# ver9.net
KiCad netlist of a schematic drawn in EAGLE
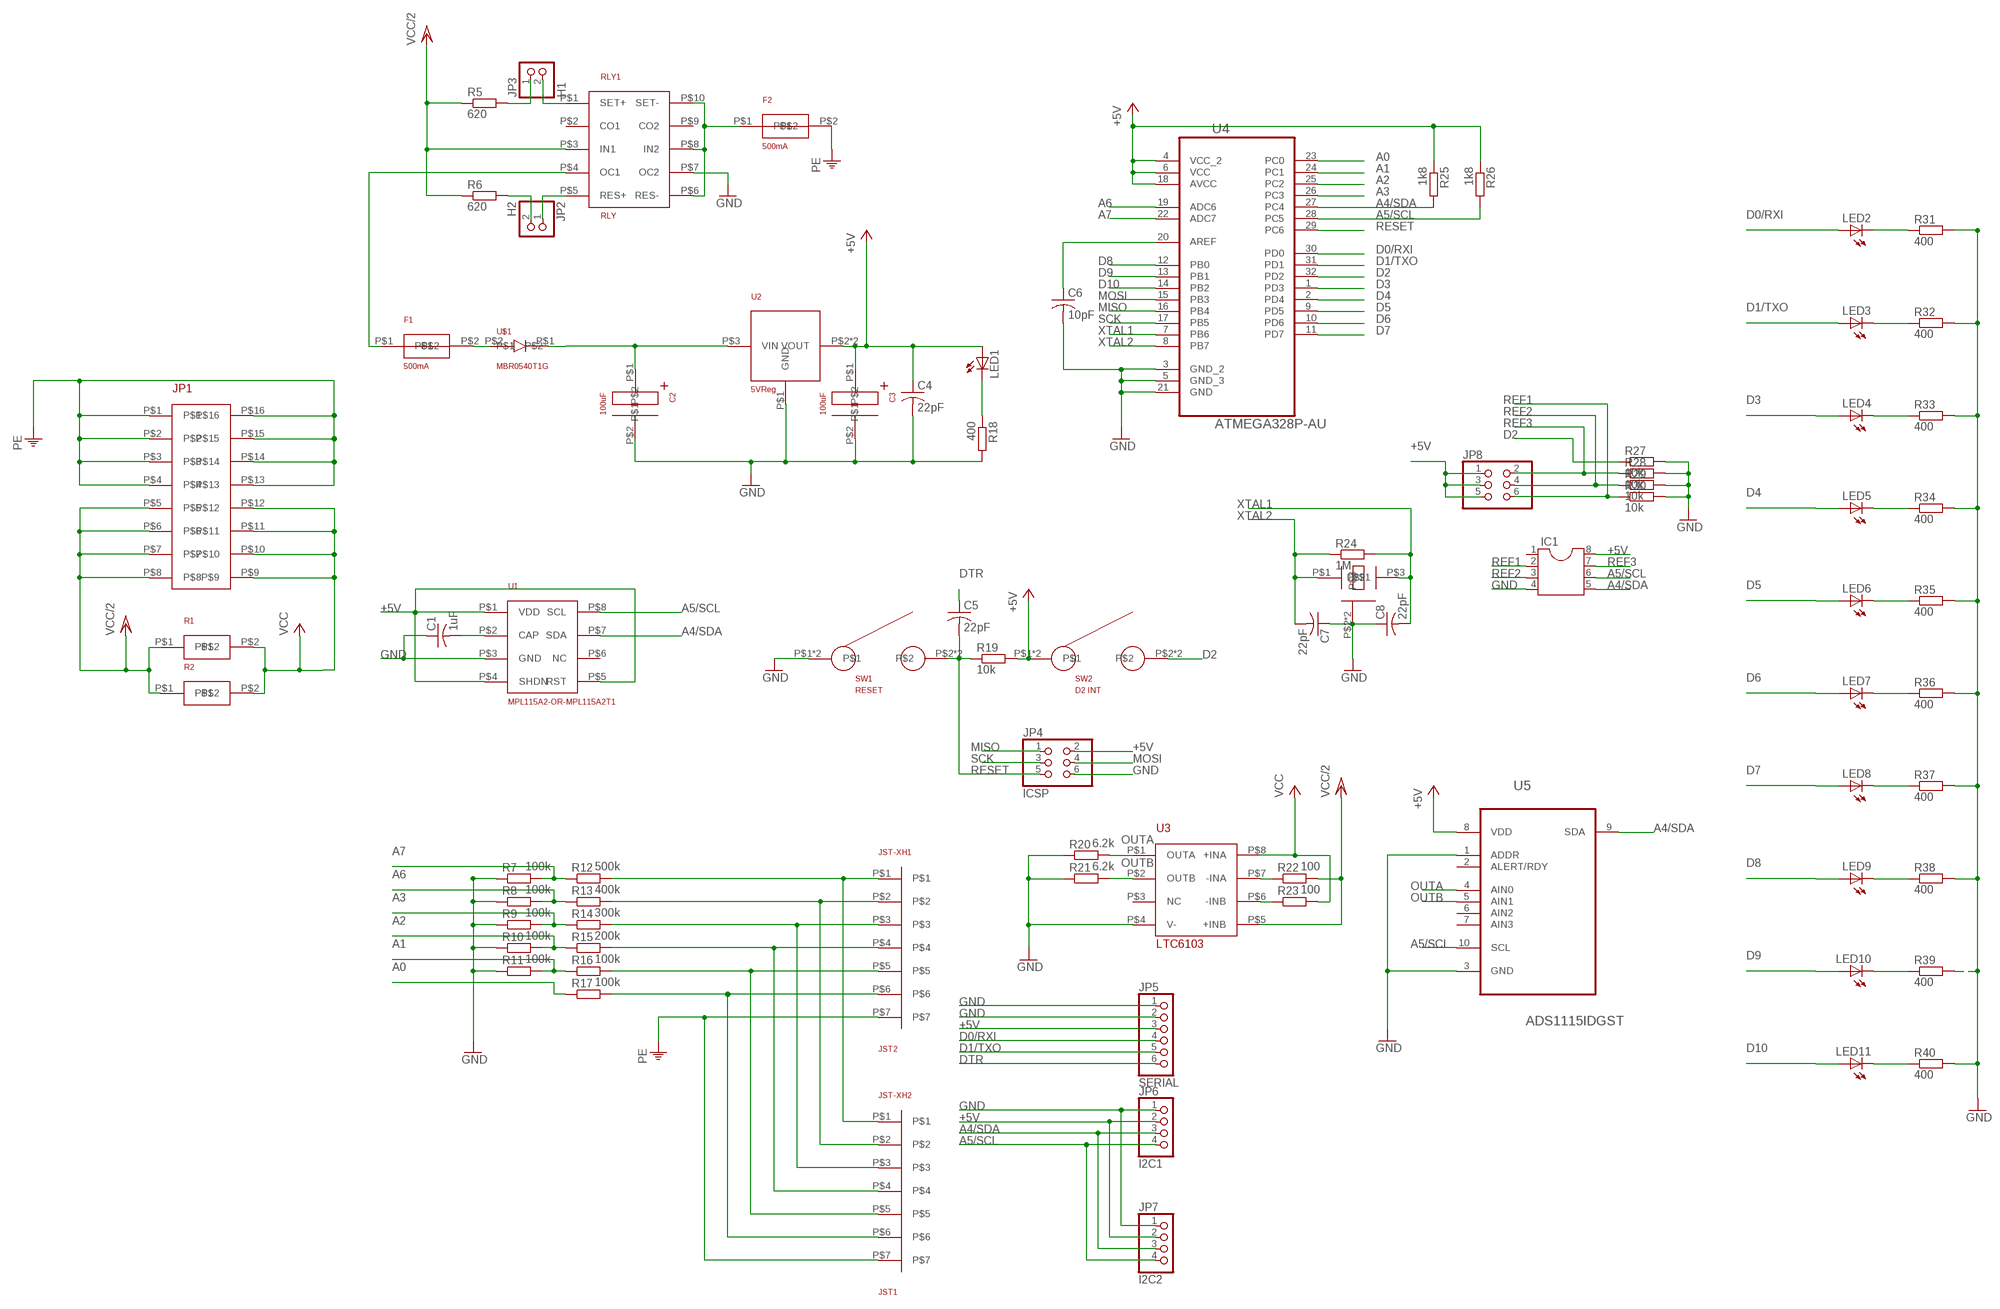
[diagram p0: schematic, sheet 1]

(export (version "E")
  (design (tool "Eeschema 10.0.6"))
  (components
    (comp (ref "C1")
      (value "1uF")
      (footprint "eagle-import:C1206")
      (libsource (lib "eagle-import") (part "C-USC1206"))
    )
    (comp (ref "C2")
      (value "100uF")
      (footprint "eagle-import:EEEFTH101XAP")
      (libsource (lib "eagle-import") (part "EEEFTH101XAP"))
    )
    (comp (ref "C3")
      (value "100uF")
      (footprint "eagle-import:EEEFTH101XAP")
      (libsource (lib "eagle-import") (part "EEEFTH101XAP"))
    )
    (comp (ref "C4")
      (value "22pF")
      (footprint "eagle-import:C1206")
      (libsource (lib "eagle-import") (part "C-USC1206"))
    )
    (comp (ref "C5")
      (value "22pF")
      (footprint "eagle-import:C1206")
      (libsource (lib "eagle-import") (part "C-USC1206"))
    )
    (comp (ref "C6")
      (value "10pF")
      (footprint "eagle-import:C1206")
      (libsource (lib "eagle-import") (part "C-USC1206"))
    )
    (comp (ref "C7")
      (value "22pF")
      (footprint "eagle-import:C1206")
      (libsource (lib "eagle-import") (part "C-USC1206"))
    )
    (comp (ref "C8")
      (value "22pF")
      (footprint "eagle-import:C1206")
      (libsource (lib "eagle-import") (part "C-USC1206"))
    )
    (comp (ref "F1")
      (value "500mA")
      (footprint "eagle-import:MF-MSMF050-2")
      (libsource (lib "eagle-import") (part "MF-MSMF050-2"))
    )
    (comp (ref "F2")
      (value "500mA")
      (footprint "eagle-import:0154.500DR-FUSE-0453.500")
      (libsource (lib "eagle-import") (part "0154.500DR-FUSE-0453.500"))
    )
    (comp (ref "IC1")
      (value "DIL8S")
      (footprint "eagle-import:SOCKET-08")
      (libsource (lib "eagle-import") (part "DIL8S"))
    )
    (comp (ref "JP1")
      (value "39-29-1167-MOLEX")
      (footprint "eagle-import:39-29-1167-MOLEX")
      (libsource (lib "eagle-import") (part "39-29-1167-MOLEX"))
    )
    (comp (ref "JP2")
      (value "H2")
      (footprint "eagle-import:1X02")
      (libsource (lib "eagle-import") (part "PINHD-1X2"))
    )
    (comp (ref "JP3")
      (value "H1")
      (footprint "eagle-import:1X02")
      (libsource (lib "eagle-import") (part "PINHD-1X2"))
    )
    (comp (ref "JP4")
      (value "ICSP")
      (footprint "eagle-import:2X03")
      (libsource (lib "eagle-import") (part "PINHD-2X3"))
    )
    (comp (ref "JP5")
      (value "SERIAL")
      (footprint "eagle-import:1X06")
      (libsource (lib "eagle-import") (part "PINHD-1X6"))
    )
    (comp (ref "JP6")
      (value "I2C1")
      (footprint "eagle-import:1X04")
      (libsource (lib "eagle-import") (part "PINHD-1X4"))
    )
    (comp (ref "JP7")
      (value "I2C2")
      (footprint "eagle-import:1X04")
      (libsource (lib "eagle-import") (part "PINHD-1X4"))
    )
    (comp (ref "JP8")
      (value "PINHD-2X3")
      (footprint "eagle-import:2X03")
      (libsource (lib "eagle-import") (part "PINHD-2X3"))
    )
    (comp (ref "JST-XH1")
      (value "JST2")
      (footprint "eagle-import:JSTXH-7PIN")
      (libsource (lib "eagle-import") (part "JSTXH-7PIN"))
    )
    (comp (ref "JST-XH2")
      (value "JST1")
      (footprint "eagle-import:JSTXH-7PIN")
      (libsource (lib "eagle-import") (part "JSTXH-7PIN"))
    )
    (comp (ref "LED1")
      (value "LED1206")
      (footprint "eagle-import:LED-1206")
      (libsource (lib "eagle-import") (part "LED1206"))
    )
    (comp (ref "LED2")
      (value "LED1206")
      (footprint "eagle-import:LED-1206")
      (libsource (lib "eagle-import") (part "LED1206"))
    )
    (comp (ref "LED3")
      (value "LED1206")
      (footprint "eagle-import:LED-1206")
      (libsource (lib "eagle-import") (part "LED1206"))
    )
    (comp (ref "LED4")
      (value "LED1206")
      (footprint "eagle-import:LED-1206")
      (libsource (lib "eagle-import") (part "LED1206"))
    )
    (comp (ref "LED5")
      (value "LED1206")
      (footprint "eagle-import:LED-1206")
      (libsource (lib "eagle-import") (part "LED1206"))
    )
    (comp (ref "LED6")
      (value "LED1206")
      (footprint "eagle-import:LED-1206")
      (libsource (lib "eagle-import") (part "LED1206"))
    )
    (comp (ref "LED7")
      (value "LED1206")
      (footprint "eagle-import:LED-1206")
      (libsource (lib "eagle-import") (part "LED1206"))
    )
    (comp (ref "LED8")
      (value "LED1206")
      (footprint "eagle-import:LED-1206")
      (libsource (lib "eagle-import") (part "LED1206"))
    )
    (comp (ref "LED9")
      (value "LED1206")
      (footprint "eagle-import:LED-1206")
      (libsource (lib "eagle-import") (part "LED1206"))
    )
    (comp (ref "LED10")
      (value "LED1206")
      (footprint "eagle-import:LED-1206")
      (libsource (lib "eagle-import") (part "LED1206"))
    )
    (comp (ref "LED11")
      (value "LED1206")
      (footprint "eagle-import:LED-1206")
      (libsource (lib "eagle-import") (part "LED1206"))
    )
    (comp (ref "R1")
      (value "OARSXPR002FLF")
      (footprint "eagle-import:OARSXPR002FLF")
      (libsource (lib "eagle-import") (part "OARSXPR002FLF"))
    )
    (comp (ref "R2")
      (value "OARSXPR002FLF")
      (footprint "eagle-import:OARSXPR002FLF")
      (libsource (lib "eagle-import") (part "OARSXPR002FLF"))
    )
    (comp (ref "R5")
      (value "620")
      (footprint "eagle-import:R1206")
      (libsource (lib "eagle-import") (part "R-EU_R1206"))
    )
    (comp (ref "R6")
      (value "620")
      (footprint "eagle-import:R1206")
      (libsource (lib "eagle-import") (part "R-EU_R1206"))
    )
    (comp (ref "R7")
      (value "100k")
      (footprint "eagle-import:R1206")
      (libsource (lib "eagle-import") (part "R-EU_R1206"))
    )
    (comp (ref "R8")
      (value "100k")
      (footprint "eagle-import:R1206")
      (libsource (lib "eagle-import") (part "R-EU_R1206"))
    )
    (comp (ref "R9")
      (value "100k")
      (footprint "eagle-import:R1206")
      (libsource (lib "eagle-import") (part "R-EU_R1206"))
    )
    (comp (ref "R10")
      (value "100k")
      (footprint "eagle-import:R1206")
      (libsource (lib "eagle-import") (part "R-EU_R1206"))
    )
    (comp (ref "R11")
      (value "100k")
      (footprint "eagle-import:R1206")
      (libsource (lib "eagle-import") (part "R-EU_R1206"))
    )
    (comp (ref "R12")
      (value "500k")
      (footprint "eagle-import:R1206")
      (libsource (lib "eagle-import") (part "R-EU_R1206"))
    )
    (comp (ref "R13")
      (value "400k")
      (footprint "eagle-import:R1206")
      (libsource (lib "eagle-import") (part "R-EU_R1206"))
    )
    (comp (ref "R14")
      (value "300k")
      (footprint "eagle-import:R1206")
      (libsource (lib "eagle-import") (part "R-EU_R1206"))
    )
    (comp (ref "R15")
      (value "200k")
      (footprint "eagle-import:R1206")
      (libsource (lib "eagle-import") (part "R-EU_R1206"))
    )
    (comp (ref "R16")
      (value "100k")
      (footprint "eagle-import:R1206")
      (libsource (lib "eagle-import") (part "R-EU_R1206"))
    )
    (comp (ref "R17")
      (value "100k")
      (footprint "eagle-import:R1206")
      (libsource (lib "eagle-import") (part "R-EU_R1206"))
    )
    (comp (ref "R18")
      (value "400")
      (footprint "eagle-import:R1206")
      (libsource (lib "eagle-import") (part "R-EU_R1206"))
    )
    (comp (ref "R19")
      (value "10k")
      (footprint "eagle-import:R1206")
      (libsource (lib "eagle-import") (part "R-EU_R1206"))
    )
    (comp (ref "R20")
      (value "6.2k")
      (footprint "eagle-import:R1206")
      (libsource (lib "eagle-import") (part "R-EU_R1206"))
    )
    (comp (ref "R21")
      (value "6.2k")
      (footprint "eagle-import:R1206")
      (libsource (lib "eagle-import") (part "R-EU_R1206"))
    )
    (comp (ref "R22")
      (value "100")
      (footprint "eagle-import:R1206")
      (libsource (lib "eagle-import") (part "R-EU_R1206"))
    )
    (comp (ref "R23")
      (value "100")
      (footprint "eagle-import:R1206")
      (libsource (lib "eagle-import") (part "R-EU_R1206"))
    )
    (comp (ref "R24")
      (value "1M")
      (footprint "eagle-import:R1206")
      (libsource (lib "eagle-import") (part "R-EU_R1206"))
    )
    (comp (ref "R25")
      (value "1k8")
      (footprint "eagle-import:R1206")
      (libsource (lib "eagle-import") (part "R-EU_R1206"))
    )
    (comp (ref "R26")
      (value "1k8")
      (footprint "eagle-import:R1206")
      (libsource (lib "eagle-import") (part "R-EU_R1206"))
    )
    (comp (ref "R27")
      (value "10k")
      (footprint "eagle-import:R1206")
      (libsource (lib "eagle-import") (part "R-EU_R1206"))
    )
    (comp (ref "R28")
      (value "10k")
      (footprint "eagle-import:R1206")
      (libsource (lib "eagle-import") (part "R-EU_R1206"))
    )
    (comp (ref "R29")
      (value "10k")
      (footprint "eagle-import:R1206")
      (libsource (lib "eagle-import") (part "R-EU_R1206"))
    )
    (comp (ref "R30")
      (value "10k")
      (footprint "eagle-import:R1206")
      (libsource (lib "eagle-import") (part "R-EU_R1206"))
    )
    (comp (ref "R31")
      (value "400")
      (footprint "eagle-import:R1206")
      (libsource (lib "eagle-import") (part "R-EU_R1206"))
    )
    (comp (ref "R32")
      (value "400")
      (footprint "eagle-import:R1206")
      (libsource (lib "eagle-import") (part "R-EU_R1206"))
    )
    (comp (ref "R33")
      (value "400")
      (footprint "eagle-import:R1206")
      (libsource (lib "eagle-import") (part "R-EU_R1206"))
    )
    (comp (ref "R34")
      (value "400")
      (footprint "eagle-import:R1206")
      (libsource (lib "eagle-import") (part "R-EU_R1206"))
    )
    (comp (ref "R35")
      (value "400")
      (footprint "eagle-import:R1206")
      (libsource (lib "eagle-import") (part "R-EU_R1206"))
    )
    (comp (ref "R36")
      (value "400")
      (footprint "eagle-import:R1206")
      (libsource (lib "eagle-import") (part "R-EU_R1206"))
    )
    (comp (ref "R37")
      (value "400")
      (footprint "eagle-import:R1206")
      (libsource (lib "eagle-import") (part "R-EU_R1206"))
    )
    (comp (ref "R38")
      (value "400")
      (footprint "eagle-import:R1206")
      (libsource (lib "eagle-import") (part "R-EU_R1206"))
    )
    (comp (ref "R39")
      (value "400")
      (footprint "eagle-import:R1206")
      (libsource (lib "eagle-import") (part "R-EU_R1206"))
    )
    (comp (ref "R40")
      (value "400")
      (footprint "eagle-import:R1206")
      (libsource (lib "eagle-import") (part "R-EU_R1206"))
    )
    (comp (ref "RLY1")
      (value "RLY")
      (footprint "eagle-import:3-1393788-3")
      (libsource (lib "eagle-import") (part "3-1393788-3"))
    )
    (comp (ref "SW1")
      (value "RESET")
      (footprint "eagle-import:MC32829")
      (libsource (lib "eagle-import") (part "MC32829"))
    )
    (comp (ref "SW2")
      (value "D2 INT")
      (footprint "eagle-import:MC32829")
      (libsource (lib "eagle-import") (part "MC32829"))
    )
    (comp (ref "U$1")
      (value "MBR0540T1G")
      (footprint "eagle-import:MBR0540T1G")
      (libsource (lib "eagle-import") (part "MBR0540T1G"))
    )
    (comp (ref "U1")
      (value "MPL115A2-OR-MPL115A2T1")
      (footprint "eagle-import:MPL115A2-OR-MPL115A2T1")
      (libsource (lib "eagle-import") (part "MPL115A2-OR-MPL115A2T1"))
    )
    (comp (ref "U2")
      (value "5VReg")
      (footprint "eagle-import:NX1117C50Z")
      (libsource (lib "eagle-import") (part "NX1117C50Z"))
    )
    (comp (ref "U3")
      (value "LTC6103")
      (footprint "eagle-import:LTC6103CMS8#PBF")
      (libsource (lib "eagle-import") (part "LTC6103CMS8#PBF"))
    )
    (comp (ref "U4")
      (value "ATMEGA328P-AU")
      (footprint "eagle-import:QFP80P900X900X120-32N")
      (libsource (lib "eagle-import") (part "ATMEGA328P-AU"))
    )
    (comp (ref "U5")
      (value "ADS1115IDGST")
      (footprint "eagle-import:SOP50P490X110-10N")
      (libsource (lib "eagle-import") (part "ADS1115IDGST"))
    )
    (comp (ref "XT1")
      (value "ABMM2-16.000MHZ-E2-T")
      (footprint "eagle-import:ABMM2-16.000MHZ-E2-T")
      (libsource (lib "eagle-import") (part "ABMM2-16.000MHZ-E2-T"))
    )
  )
  (nets
    (net (code "1") (name "+5V") (class "Default")
      (node (ref "C3") (pin "P$1") (pinfunction "P$1_P$1") (pintype "bidirectional"))
      (node (ref "C4") (pin "1") (pinfunction "1_1") (pintype "passive"))
      (node (ref "IC1") (pin "8") (pinfunction "8_8") (pintype "passive"))
      (node (ref "JP4") (pin "2") (pinfunction "2_2") (pintype "passive"))
      (node (ref "JP5") (pin "3") (pinfunction "3_3") (pintype "passive"))
      (node (ref "JP6") (pin "2") (pinfunction "2_2") (pintype "passive"))
      (node (ref "JP7") (pin "2") (pinfunction "2_2") (pintype "passive"))
      (node (ref "JP8") (pin "1") (pinfunction "1_1") (pintype "passive"))
      (node (ref "JP8") (pin "3") (pinfunction "3_3") (pintype "passive"))
      (node (ref "JP8") (pin "5") (pinfunction "5_5") (pintype "passive"))
      (node (ref "LED1") (pin "A") (pinfunction "A_A") (pintype "passive"))
      (node (ref "R19") (pin "2") (pinfunction "2_2") (pintype "passive"))
      (node (ref "R25") (pin "1") (pinfunction "1_1") (pintype "passive"))
      (node (ref "R26") (pin "1") (pinfunction "1_1") (pintype "passive"))
      (node (ref "SW2") (pin "P$1") (pinfunction "P$1_P$1") (pintype "bidirectional"))
      (node (ref "SW2") (pin "P$4") (pinfunction "P$1_P$4") (pintype "bidirectional"))
      (node (ref "U1") (pin "P$1") (pinfunction "VDD_P$1") (pintype "bidirectional"))
      (node (ref "U1") (pin "P$4") (pinfunction "SHDN_P$4") (pintype "bidirectional"))
      (node (ref "U1") (pin "P$5") (pinfunction "RST_P$5") (pintype "bidirectional"))
      (node (ref "U2") (pin "P$2") (pinfunction "VOUT_P$2") (pintype "bidirectional"))
      (node (ref "U2") (pin "P$4") (pinfunction "VOUT_P$4") (pintype "bidirectional"))
      (node (ref "U4") (pin "18") (pinfunction "AVCC_18") (pintype "power_in"))
      (node (ref "U4") (pin "4") (pinfunction "VCC_2_4") (pintype "power_in"))
      (node (ref "U4") (pin "6") (pinfunction "VCC_6") (pintype "power_in"))
      (node (ref "U5") (pin "8") (pinfunction "VDD_8") (pintype "power_in"))
    )
    (net (code "2") (name "/A0") (class "Default")
      (node (ref "R17") (pin "1") (pinfunction "1_1") (pintype "passive"))
      (node (ref "U4") (pin "23") (pinfunction "PC0_23") (pintype "bidirectional"))
    )
    (net (code "3") (name "/A1") (class "Default")
      (node (ref "R11") (pin "2") (pinfunction "2_2") (pintype "passive"))
      (node (ref "R16") (pin "1") (pinfunction "1_1") (pintype "passive"))
      (node (ref "U4") (pin "24") (pinfunction "PC1_24") (pintype "bidirectional"))
    )
    (net (code "4") (name "/A2") (class "Default")
      (node (ref "R10") (pin "2") (pinfunction "2_2") (pintype "passive"))
      (node (ref "R15") (pin "1") (pinfunction "1_1") (pintype "passive"))
      (node (ref "U4") (pin "25") (pinfunction "PC2_25") (pintype "bidirectional"))
    )
    (net (code "5") (name "/A3") (class "Default")
      (node (ref "R14") (pin "1") (pinfunction "1_1") (pintype "passive"))
      (node (ref "R9") (pin "2") (pinfunction "2_2") (pintype "passive"))
      (node (ref "U4") (pin "26") (pinfunction "PC3_26") (pintype "bidirectional"))
    )
    (net (code "6") (name "/A4{slash}SDA") (class "Default")
      (node (ref "IC1") (pin "5") (pinfunction "5_5") (pintype "passive"))
      (node (ref "JP6") (pin "3") (pinfunction "3_3") (pintype "passive"))
      (node (ref "JP7") (pin "3") (pinfunction "3_3") (pintype "passive"))
      (node (ref "R25") (pin "2") (pinfunction "2_2") (pintype "passive"))
      (node (ref "U1") (pin "P$7") (pinfunction "SDA_P$7") (pintype "bidirectional"))
      (node (ref "U4") (pin "27") (pinfunction "PC4_27") (pintype "bidirectional"))
      (node (ref "U5") (pin "9") (pinfunction "SDA_9") (pintype "bidirectional"))
    )
    (net (code "7") (name "/A5{slash}SCL") (class "Default")
      (node (ref "IC1") (pin "6") (pinfunction "6_6") (pintype "passive"))
      (node (ref "JP6") (pin "4") (pinfunction "4_4") (pintype "passive"))
      (node (ref "JP7") (pin "4") (pinfunction "4_4") (pintype "passive"))
      (node (ref "R26") (pin "2") (pinfunction "2_2") (pintype "passive"))
      (node (ref "U1") (pin "P$8") (pinfunction "SCL_P$8") (pintype "bidirectional"))
      (node (ref "U4") (pin "28") (pinfunction "PC5_28") (pintype "bidirectional"))
      (node (ref "U5") (pin "10") (pinfunction "SCL_10") (pintype "input"))
    )
    (net (code "8") (name "/A6") (class "Default")
      (node (ref "R13") (pin "1") (pinfunction "1_1") (pintype "passive"))
      (node (ref "R8") (pin "2") (pinfunction "2_2") (pintype "passive"))
      (node (ref "U4") (pin "19") (pinfunction "ADC6_19") (pintype "input"))
    )
    (net (code "9") (name "/A7") (class "Default")
      (node (ref "R12") (pin "1") (pinfunction "1_1") (pintype "passive"))
      (node (ref "R7") (pin "2") (pinfunction "2_2") (pintype "passive"))
      (node (ref "U4") (pin "22") (pinfunction "ADC7_22") (pintype "input"))
    )
    (net (code "10") (name "/D0{slash}RXI") (class "Default")
      (node (ref "JP5") (pin "4") (pinfunction "4_4") (pintype "passive"))
      (node (ref "LED2") (pin "A") (pinfunction "A_A") (pintype "passive"))
      (node (ref "U4") (pin "30") (pinfunction "PD0_30") (pintype "bidirectional"))
    )
    (net (code "11") (name "/D1{slash}TXO") (class "Default")
      (node (ref "JP5") (pin "5") (pinfunction "5_5") (pintype "passive"))
      (node (ref "LED3") (pin "A") (pinfunction "A_A") (pintype "passive"))
      (node (ref "U4") (pin "31") (pinfunction "PD1_31") (pintype "bidirectional"))
    )
    (net (code "12") (name "/D2") (class "Default")
      (node (ref "R27") (pin "1") (pinfunction "1_1") (pintype "passive"))
      (node (ref "SW2") (pin "P$2") (pinfunction "P$2_P$2") (pintype "bidirectional"))
      (node (ref "SW2") (pin "P$3") (pinfunction "P$2_P$3") (pintype "bidirectional"))
      (node (ref "U4") (pin "32") (pinfunction "PD2_32") (pintype "bidirectional"))
    )
    (net (code "13") (name "/D3") (class "Default")
      (node (ref "LED4") (pin "A") (pinfunction "A_A") (pintype "passive"))
      (node (ref "U4") (pin "1") (pinfunction "PD3_1") (pintype "bidirectional"))
    )
    (net (code "14") (name "/D4") (class "Default")
      (node (ref "LED5") (pin "A") (pinfunction "A_A") (pintype "passive"))
      (node (ref "U4") (pin "2") (pinfunction "PD4_2") (pintype "bidirectional"))
    )
    (net (code "15") (name "/D5") (class "Default")
      (node (ref "LED6") (pin "A") (pinfunction "A_A") (pintype "passive"))
      (node (ref "U4") (pin "9") (pinfunction "PD5_9") (pintype "bidirectional"))
    )
    (net (code "16") (name "/D6") (class "Default")
      (node (ref "LED7") (pin "A") (pinfunction "A_A") (pintype "passive"))
      (node (ref "U4") (pin "10") (pinfunction "PD6_10") (pintype "bidirectional"))
    )
    (net (code "17") (name "/D7") (class "Default")
      (node (ref "LED8") (pin "A") (pinfunction "A_A") (pintype "passive"))
      (node (ref "U4") (pin "11") (pinfunction "PD7_11") (pintype "bidirectional"))
    )
    (net (code "18") (name "/D8") (class "Default")
      (node (ref "LED9") (pin "A") (pinfunction "A_A") (pintype "passive"))
      (node (ref "U4") (pin "12") (pinfunction "PB0_12") (pintype "bidirectional"))
    )
    (net (code "19") (name "/D9") (class "Default")
      (node (ref "LED10") (pin "A") (pinfunction "A_A") (pintype "passive"))
      (node (ref "U4") (pin "13") (pinfunction "PB1_13") (pintype "bidirectional"))
    )
    (net (code "20") (name "/D10") (class "Default")
      (node (ref "LED11") (pin "A") (pinfunction "A_A") (pintype "passive"))
      (node (ref "U4") (pin "14") (pinfunction "PB2_14") (pintype "bidirectional"))
    )
    (net (code "21") (name "/DTR") (class "Default")
      (node (ref "C5") (pin "1") (pinfunction "1_1") (pintype "passive"))
      (node (ref "JP5") (pin "6") (pinfunction "6_6") (pintype "passive"))
    )
    (net (code "22") (name "/MISO") (class "Default")
      (node (ref "JP4") (pin "1") (pinfunction "1_1") (pintype "passive"))
      (node (ref "U4") (pin "16") (pinfunction "PB4_16") (pintype "bidirectional"))
    )
    (net (code "23") (name "/MOSI") (class "Default")
      (node (ref "JP4") (pin "4") (pinfunction "4_4") (pintype "passive"))
      (node (ref "U4") (pin "15") (pinfunction "PB3_15") (pintype "bidirectional"))
    )
    (net (code "24") (name "/OUTA") (class "Default")
      (node (ref "R20") (pin "2") (pinfunction "2_2") (pintype "passive"))
      (node (ref "U3") (pin "P$1") (pinfunction "OUTA_P$1") (pintype "bidirectional"))
      (node (ref "U5") (pin "4") (pinfunction "AIN0_4") (pintype "input"))
    )
    (net (code "25") (name "/OUTB") (class "Default")
      (node (ref "R21") (pin "2") (pinfunction "2_2") (pintype "passive"))
      (node (ref "U3") (pin "P$2") (pinfunction "OUTB_P$2") (pintype "bidirectional"))
      (node (ref "U5") (pin "5") (pinfunction "AIN1_5") (pintype "input"))
    )
    (net (code "26") (name "/REF1") (class "Default")
      (node (ref "IC1") (pin "2") (pinfunction "2_2") (pintype "passive"))
      (node (ref "JP8") (pin "6") (pinfunction "6_6") (pintype "passive"))
      (node (ref "R30") (pin "1") (pinfunction "1_1") (pintype "passive"))
    )
    (net (code "27") (name "/REF2") (class "Default")
      (node (ref "IC1") (pin "3") (pinfunction "3_3") (pintype "passive"))
      (node (ref "JP8") (pin "4") (pinfunction "4_4") (pintype "passive"))
      (node (ref "R29") (pin "1") (pinfunction "1_1") (pintype "passive"))
    )
    (net (code "28") (name "/REF3") (class "Default")
      (node (ref "IC1") (pin "7") (pinfunction "7_7") (pintype "passive"))
      (node (ref "JP8") (pin "2") (pinfunction "2_2") (pintype "passive"))
      (node (ref "R28") (pin "1") (pinfunction "1_1") (pintype "passive"))
    )
    (net (code "29") (name "/RESET") (class "Default")
      (node (ref "C5") (pin "2") (pinfunction "2_2") (pintype "passive"))
      (node (ref "JP4") (pin "5") (pinfunction "5_5") (pintype "passive"))
      (node (ref "R19") (pin "1") (pinfunction "1_1") (pintype "passive"))
      (node (ref "SW1") (pin "P$2") (pinfunction "P$2_P$2") (pintype "bidirectional"))
      (node (ref "SW1") (pin "P$3") (pinfunction "P$2_P$3") (pintype "bidirectional"))
      (node (ref "U4") (pin "29") (pinfunction "PC6_29") (pintype "bidirectional"))
    )
    (net (code "30") (name "/SCK") (class "Default")
      (node (ref "JP4") (pin "3") (pinfunction "3_3") (pintype "passive"))
      (node (ref "U4") (pin "17") (pinfunction "PB5_17") (pintype "bidirectional"))
    )
    (net (code "31") (name "/XTAL1") (class "Default")
      (node (ref "C8") (pin "2") (pinfunction "2_2") (pintype "passive"))
      (node (ref "R24") (pin "2") (pinfunction "2_2") (pintype "passive"))
      (node (ref "U4") (pin "7") (pinfunction "PB6_7") (pintype "bidirectional"))
      (node (ref "XT1") (pin "P$3") (pinfunction "P$2_P$3") (pintype "bidirectional"))
    )
    (net (code "32") (name "/XTAL2") (class "Default")
      (node (ref "C7") (pin "2") (pinfunction "2_2") (pintype "passive"))
      (node (ref "R24") (pin "1") (pinfunction "1_1") (pintype "passive"))
      (node (ref "U4") (pin "8") (pinfunction "PB7_8") (pintype "bidirectional"))
      (node (ref "XT1") (pin "P$1") (pinfunction "P$1_P$1") (pintype "bidirectional"))
    )
    (net (code "33") (name "GND") (class "Default")
      (node (ref "C1") (pin "1") (pinfunction "1_1") (pintype "passive"))
      (node (ref "C2") (pin "P$2") (pinfunction "P$2_P$2") (pintype "bidirectional"))
      (node (ref "C3") (pin "P$2") (pinfunction "P$2_P$2") (pintype "bidirectional"))
      (node (ref "C4") (pin "2") (pinfunction "2_2") (pintype "passive"))
      (node (ref "C6") (pin "2") (pinfunction "2_2") (pintype "passive"))
      (node (ref "C7") (pin "1") (pinfunction "1_1") (pintype "passive"))
      (node (ref "C8") (pin "1") (pinfunction "1_1") (pintype "passive"))
      (node (ref "IC1") (pin "4") (pinfunction "4_4") (pintype "passive"))
      (node (ref "JP4") (pin "6") (pinfunction "6_6") (pintype "passive"))
      (node (ref "JP5") (pin "1") (pinfunction "1_1") (pintype "passive"))
      (node (ref "JP5") (pin "2") (pinfunction "2_2") (pintype "passive"))
      (node (ref "JP6") (pin "1") (pinfunction "1_1") (pintype "passive"))
      (node (ref "JP7") (pin "1") (pinfunction "1_1") (pintype "passive"))
      (node (ref "R10") (pin "1") (pinfunction "1_1") (pintype "passive"))
      (node (ref "R11") (pin "1") (pinfunction "1_1") (pintype "passive"))
      (node (ref "R18") (pin "2") (pinfunction "2_2") (pintype "passive"))
      (node (ref "R20") (pin "1") (pinfunction "1_1") (pintype "passive"))
      (node (ref "R21") (pin "1") (pinfunction "1_1") (pintype "passive"))
      (node (ref "R27") (pin "2") (pinfunction "2_2") (pintype "passive"))
      (node (ref "R28") (pin "2") (pinfunction "2_2") (pintype "passive"))
      (node (ref "R29") (pin "2") (pinfunction "2_2") (pintype "passive"))
      (node (ref "R30") (pin "2") (pinfunction "2_2") (pintype "passive"))
      (node (ref "R31") (pin "2") (pinfunction "2_2") (pintype "passive"))
      (node (ref "R32") (pin "2") (pinfunction "2_2") (pintype "passive"))
      (node (ref "R33") (pin "2") (pinfunction "2_2") (pintype "passive"))
      (node (ref "R34") (pin "2") (pinfunction "2_2") (pintype "passive"))
      (node (ref "R35") (pin "2") (pinfunction "2_2") (pintype "passive"))
      (node (ref "R36") (pin "2") (pinfunction "2_2") (pintype "passive"))
      (node (ref "R37") (pin "2") (pinfunction "2_2") (pintype "passive"))
      (node (ref "R38") (pin "2") (pinfunction "2_2") (pintype "passive"))
      (node (ref "R39") (pin "2") (pinfunction "2_2") (pintype "passive"))
      (node (ref "R40") (pin "2") (pinfunction "2_2") (pintype "passive"))
      (node (ref "R7") (pin "1") (pinfunction "1_1") (pintype "passive"))
      (node (ref "R8") (pin "1") (pinfunction "1_1") (pintype "passive"))
      (node (ref "R9") (pin "1") (pinfunction "1_1") (pintype "passive"))
      (node (ref "RLY1") (pin "P$7") (pinfunction "OC2_P$7") (pintype "bidirectional"))
      (node (ref "SW1") (pin "P$1") (pinfunction "P$1_P$1") (pintype "bidirectional"))
      (node (ref "SW1") (pin "P$4") (pinfunction "P$1_P$4") (pintype "bidirectional"))
      (node (ref "U1") (pin "P$3") (pinfunction "GND_P$3") (pintype "bidirectional"))
      (node (ref "U2") (pin "P$1") (pinfunction "GND_P$1") (pintype "bidirectional"))
      (node (ref "U3") (pin "P$4") (pinfunction "V-_P$4") (pintype "bidirectional"))
      (node (ref "U4") (pin "21") (pinfunction "GND_21") (pintype "passive"))
      (node (ref "U4") (pin "3") (pinfunction "GND_2_3") (pintype "passive"))
      (node (ref "U4") (pin "5") (pinfunction "GND_3_5") (pintype "passive"))
      (node (ref "U5") (pin "1") (pinfunction "ADDR_1") (pintype "input"))
      (node (ref "U5") (pin "3") (pinfunction "GND_3") (pintype "passive"))
      (node (ref "XT1") (pin "P$2") (pinfunction "P$3_P$2") (pintype "bidirectional"))
      (node (ref "XT1") (pin "P$4") (pinfunction "P$3_P$4") (pintype "bidirectional"))
    )
    (net (code "34") (name "Net-(F1-PadP$2)") (class "Default")
      (node (ref "F1") (pin "P$2") (pinfunction "P$2_P$2") (pintype "bidirectional"))
      (node (ref "U$1") (pin "P$2") (pinfunction "P$2_P$2") (pintype "bidirectional"))
    )
    (net (code "35") (name "Net-(JP2-Pad2)") (class "Default")
      (node (ref "JP2") (pin "2") (pinfunction "2_2") (pintype "passive"))
      (node (ref "R6") (pin "2") (pinfunction "2_2") (pintype "passive"))
    )
    (net (code "36") (name "Net-(JP3-Pad1)") (class "Default")
      (node (ref "JP3") (pin "1") (pinfunction "1_1") (pintype "passive"))
      (node (ref "R5") (pin "2") (pinfunction "2_2") (pintype "passive"))
    )
    (net (code "37") (name "Net-(JST-XH1-PadP$1)") (class "Default")
      (node (ref "JST-XH1") (pin "P$1") (pinfunction "P$1_P$1") (pintype "bidirectional"))
      (node (ref "JST-XH2") (pin "P$1") (pinfunction "P$1_P$1") (pintype "bidirectional"))
      (node (ref "R12") (pin "2") (pinfunction "2_2") (pintype "passive"))
    )
    (net (code "38") (name "Net-(JST-XH1-PadP$2)") (class "Default")
      (node (ref "JST-XH1") (pin "P$2") (pinfunction "P$2_P$2") (pintype "bidirectional"))
      (node (ref "JST-XH2") (pin "P$2") (pinfunction "P$2_P$2") (pintype "bidirectional"))
      (node (ref "R13") (pin "2") (pinfunction "2_2") (pintype "passive"))
    )
    (net (code "39") (name "Net-(JST-XH1-PadP$3)") (class "Default")
      (node (ref "JST-XH1") (pin "P$3") (pinfunction "P$3_P$3") (pintype "bidirectional"))
      (node (ref "JST-XH2") (pin "P$3") (pinfunction "P$3_P$3") (pintype "bidirectional"))
      (node (ref "R14") (pin "2") (pinfunction "2_2") (pintype "passive"))
    )
    (net (code "40") (name "Net-(JST-XH1-PadP$4)") (class "Default")
      (node (ref "JST-XH1") (pin "P$4") (pinfunction "P$4_P$4") (pintype "bidirectional"))
      (node (ref "JST-XH2") (pin "P$4") (pinfunction "P$4_P$4") (pintype "bidirectional"))
      (node (ref "R15") (pin "2") (pinfunction "2_2") (pintype "passive"))
    )
    (net (code "41") (name "Net-(JST-XH1-PadP$5)") (class "Default")
      (node (ref "JST-XH1") (pin "P$5") (pinfunction "P$5_P$5") (pintype "bidirectional"))
      (node (ref "JST-XH2") (pin "P$5") (pinfunction "P$5_P$5") (pintype "bidirectional"))
      (node (ref "R16") (pin "2") (pinfunction "2_2") (pintype "passive"))
    )
    (net (code "42") (name "Net-(JST-XH1-PadP$6)") (class "Default")
      (node (ref "JST-XH1") (pin "P$6") (pinfunction "P$6_P$6") (pintype "bidirectional"))
      (node (ref "JST-XH2") (pin "P$6") (pinfunction "P$6_P$6") (pintype "bidirectional"))
      (node (ref "R17") (pin "2") (pinfunction "2_2") (pintype "passive"))
    )
    (net (code "43") (name "Net-(LED1-PadC)") (class "Default")
      (node (ref "LED1") (pin "C") (pinfunction "C_C") (pintype "passive"))
      (node (ref "R18") (pin "1") (pinfunction "1_1") (pintype "passive"))
    )
    (net (code "44") (name "Net-(LED2-PadC)") (class "Default")
      (node (ref "LED2") (pin "C") (pinfunction "C_C") (pintype "passive"))
      (node (ref "R31") (pin "1") (pinfunction "1_1") (pintype "passive"))
    )
    (net (code "45") (name "Net-(LED3-PadC)") (class "Default")
      (node (ref "LED3") (pin "C") (pinfunction "C_C") (pintype "passive"))
      (node (ref "R32") (pin "1") (pinfunction "1_1") (pintype "passive"))
    )
    (net (code "46") (name "Net-(LED4-PadC)") (class "Default")
      (node (ref "LED4") (pin "C") (pinfunction "C_C") (pintype "passive"))
      (node (ref "R33") (pin "1") (pinfunction "1_1") (pintype "passive"))
    )
    (net (code "47") (name "Net-(LED5-PadC)") (class "Default")
      (node (ref "LED5") (pin "C") (pinfunction "C_C") (pintype "passive"))
      (node (ref "R34") (pin "1") (pinfunction "1_1") (pintype "passive"))
    )
    (net (code "48") (name "Net-(LED6-PadC)") (class "Default")
      (node (ref "LED6") (pin "C") (pinfunction "C_C") (pintype "passive"))
      (node (ref "R35") (pin "1") (pinfunction "1_1") (pintype "passive"))
    )
    (net (code "49") (name "Net-(LED7-PadC)") (class "Default")
      (node (ref "LED7") (pin "C") (pinfunction "C_C") (pintype "passive"))
      (node (ref "R36") (pin "1") (pinfunction "1_1") (pintype "passive"))
    )
    (net (code "50") (name "Net-(LED8-PadC)") (class "Default")
      (node (ref "LED8") (pin "C") (pinfunction "C_C") (pintype "passive"))
      (node (ref "R37") (pin "1") (pinfunction "1_1") (pintype "passive"))
    )
    (net (code "51") (name "Net-(LED9-PadC)") (class "Default")
      (node (ref "LED9") (pin "C") (pinfunction "C_C") (pintype "passive"))
      (node (ref "R38") (pin "1") (pinfunction "1_1") (pintype "passive"))
    )
    (net (code "52") (name "Net-(LED10-PadC)") (class "Default")
      (node (ref "LED10") (pin "C") (pinfunction "C_C") (pintype "passive"))
      (node (ref "R39") (pin "1") (pinfunction "1_1") (pintype "passive"))
    )
    (net (code "53") (name "Net-(LED11-PadC)") (class "Default")
      (node (ref "LED11") (pin "C") (pinfunction "C_C") (pintype "passive"))
      (node (ref "R40") (pin "1") (pinfunction "1_1") (pintype "passive"))
    )
    (net (code "54") (name "Net-(RLY1-IN2)") (class "Default")
      (node (ref "F2") (pin "P$1") (pinfunction "P$1_P$1") (pintype "bidirectional"))
      (node (ref "RLY1") (pin "P$10") (pinfunction "SET-_P$10") (pintype "bidirectional"))
      (node (ref "RLY1") (pin "P$6") (pinfunction "RES-_P$6") (pintype "bidirectional"))
      (node (ref "RLY1") (pin "P$8") (pinfunction "IN2_P$8") (pintype "bidirectional"))
    )
    (net (code "55") (name "Net-(RLY1-OC1)") (class "Default")
      (node (ref "F1") (pin "P$1") (pinfunction "P$1_P$1") (pintype "bidirectional"))
      (node (ref "RLY1") (pin "P$4") (pinfunction "OC1_P$4") (pintype "bidirectional"))
    )
    (net (code "56") (name "Net-(RLY1-RES+)") (class "Default")
      (node (ref "JP2") (pin "1") (pinfunction "1_1") (pintype "passive"))
      (node (ref "RLY1") (pin "P$5") (pinfunction "RES+_P$5") (pintype "bidirectional"))
    )
    (net (code "57") (name "Net-(RLY1-SET+)") (class "Default")
      (node (ref "JP3") (pin "2") (pinfunction "2_2") (pintype "passive"))
      (node (ref "RLY1") (pin "P$1") (pinfunction "SET+_P$1") (pintype "bidirectional"))
    )
    (net (code "58") (name "Net-(U1-CAP)") (class "Default")
      (node (ref "C1") (pin "2") (pinfunction "2_2") (pintype "passive"))
      (node (ref "U1") (pin "P$2") (pinfunction "CAP_P$2") (pintype "bidirectional"))
    )
    (net (code "59") (name "Net-(U2-VIN)") (class "Default")
      (node (ref "C2") (pin "P$1") (pinfunction "P$1_P$1") (pintype "bidirectional"))
      (node (ref "U$1") (pin "P$1") (pinfunction "P$1_P$1") (pintype "bidirectional"))
      (node (ref "U2") (pin "P$3") (pinfunction "VIN_P$3") (pintype "bidirectional"))
    )
    (net (code "60") (name "Net-(U3--INA)") (class "Default")
      (node (ref "R22") (pin "1") (pinfunction "1_1") (pintype "passive"))
      (node (ref "U3") (pin "P$7") (pinfunction "-INA_P$7") (pintype "bidirectional"))
    )
    (net (code "61") (name "Net-(U3--INB)") (class "Default")
      (node (ref "R23") (pin "1") (pinfunction "1_1") (pintype "passive"))
      (node (ref "U3") (pin "P$6") (pinfunction "-INB_P$6") (pintype "bidirectional"))
    )
    (net (code "62") (name "Net-(U4-AREF)") (class "Default")
      (node (ref "C6") (pin "1") (pinfunction "1_1") (pintype "passive"))
      (node (ref "U4") (pin "20") (pinfunction "AREF_20") (pintype "input"))
    )
    (net (code "63") (name "PE") (class "Default")
      (node (ref "F2") (pin "P$2") (pinfunction "P$2_P$2") (pintype "bidirectional"))
      (node (ref "JP1") (pin "P$1") (pinfunction "P$1_P$1") (pintype "bidirectional"))
      (node (ref "JP1") (pin "P$13") (pinfunction "P$13_P$13") (pintype "bidirectional"))
      (node (ref "JP1") (pin "P$14") (pinfunction "P$14_P$14") (pintype "bidirectional"))
      (node (ref "JP1") (pin "P$15") (pinfunction "P$15_P$15") (pintype "bidirectional"))
      (node (ref "JP1") (pin "P$16") (pinfunction "P$16_P$16") (pintype "bidirectional"))
      (node (ref "JP1") (pin "P$2") (pinfunction "P$2_P$2") (pintype "bidirectional"))
      (node (ref "JP1") (pin "P$3") (pinfunction "P$3_P$3") (pintype "bidirectional"))
      (node (ref "JP1") (pin "P$4") (pinfunction "P$4_P$4") (pintype "bidirectional"))
      (node (ref "JST-XH1") (pin "P$7") (pinfunction "P$7_P$7") (pintype "bidirectional"))
      (node (ref "JST-XH2") (pin "P$7") (pinfunction "P$7_P$7") (pintype "bidirectional"))
    )
    (net (code "64") (name "VCC") (class "Default")
      (node (ref "JP1") (pin "P$10") (pinfunction "P$10_P$10") (pintype "bidirectional"))
      (node (ref "JP1") (pin "P$11") (pinfunction "P$11_P$11") (pintype "bidirectional"))
      (node (ref "JP1") (pin "P$12") (pinfunction "P$12_P$12") (pintype "bidirectional"))
      (node (ref "JP1") (pin "P$9") (pinfunction "P$9_P$9") (pintype "bidirectional"))
      (node (ref "R1") (pin "P$2") (pinfunction "P$2_P$2") (pintype "bidirectional"))
      (node (ref "R2") (pin "P$2") (pinfunction "P$2_P$2") (pintype "bidirectional"))
      (node (ref "R23") (pin "2") (pinfunction "2_2") (pintype "passive"))
      (node (ref "U3") (pin "P$8") (pinfunction "+INA_P$8") (pintype "bidirectional"))
    )
    (net (code "65") (name "VCC{slash}2") (class "Default")
      (node (ref "JP1") (pin "P$5") (pinfunction "P$5_P$5") (pintype "bidirectional"))
      (node (ref "JP1") (pin "P$6") (pinfunction "P$6_P$6") (pintype "bidirectional"))
      (node (ref "JP1") (pin "P$7") (pinfunction "P$7_P$7") (pintype "bidirectional"))
      (node (ref "JP1") (pin "P$8") (pinfunction "P$8_P$8") (pintype "bidirectional"))
      (node (ref "R1") (pin "P$1") (pinfunction "P$1_P$1") (pintype "bidirectional"))
      (node (ref "R2") (pin "P$1") (pinfunction "P$1_P$1") (pintype "bidirectional"))
      (node (ref "R22") (pin "2") (pinfunction "2_2") (pintype "passive"))
      (node (ref "R5") (pin "1") (pinfunction "1_1") (pintype "passive"))
      (node (ref "R6") (pin "1") (pinfunction "1_1") (pintype "passive"))
      (node (ref "RLY1") (pin "P$3") (pinfunction "IN1_P$3") (pintype "bidirectional"))
      (node (ref "U3") (pin "P$5") (pinfunction "+INB_P$5") (pintype "bidirectional"))
    )
    (net (code "66") (name "unconnected-(IC1-Pad1)") (class "Default")
      (node (ref "IC1") (pin "1") (pinfunction "1_1") (pintype "passive"))
    )
    (net (code "67") (name "unconnected-(RLY1-CO1-PadP$2)") (class "Default")
      (node (ref "RLY1") (pin "P$2") (pinfunction "CO1_P$2") (pintype "bidirectional"))
    )
    (net (code "68") (name "unconnected-(RLY1-CO2-PadP$9)") (class "Default")
      (node (ref "RLY1") (pin "P$9") (pinfunction "CO2_P$9") (pintype "bidirectional"))
    )
    (net (code "69") (name "unconnected-(U1-NC-PadP$6)") (class "Default")
      (node (ref "U1") (pin "P$6") (pinfunction "NC_P$6") (pintype "bidirectional"))
    )
    (net (code "70") (name "unconnected-(U3-NC-PadP$3)") (class "Default")
      (node (ref "U3") (pin "P$3") (pinfunction "NC_P$3") (pintype "bidirectional"))
    )
    (net (code "71") (name "unconnected-(U5-AIN2-Pad6)") (class "Default")
      (node (ref "U5") (pin "6") (pinfunction "AIN2_6") (pintype "input"))
    )
    (net (code "72") (name "unconnected-(U5-AIN3-Pad7)") (class "Default")
      (node (ref "U5") (pin "7") (pinfunction "AIN3_7") (pintype "input"))
    )
    (net (code "73") (name "unconnected-(U5-ALERT{slash}RDY-Pad2)") (class "Default")
      (node (ref "U5") (pin "2") (pinfunction "ALERT/RDY_2") (pintype "input"))
    )
  )
)
